# SingleBoardCircuitRev2.net
KiCad netlist of a schematic drawn in Altium Designer
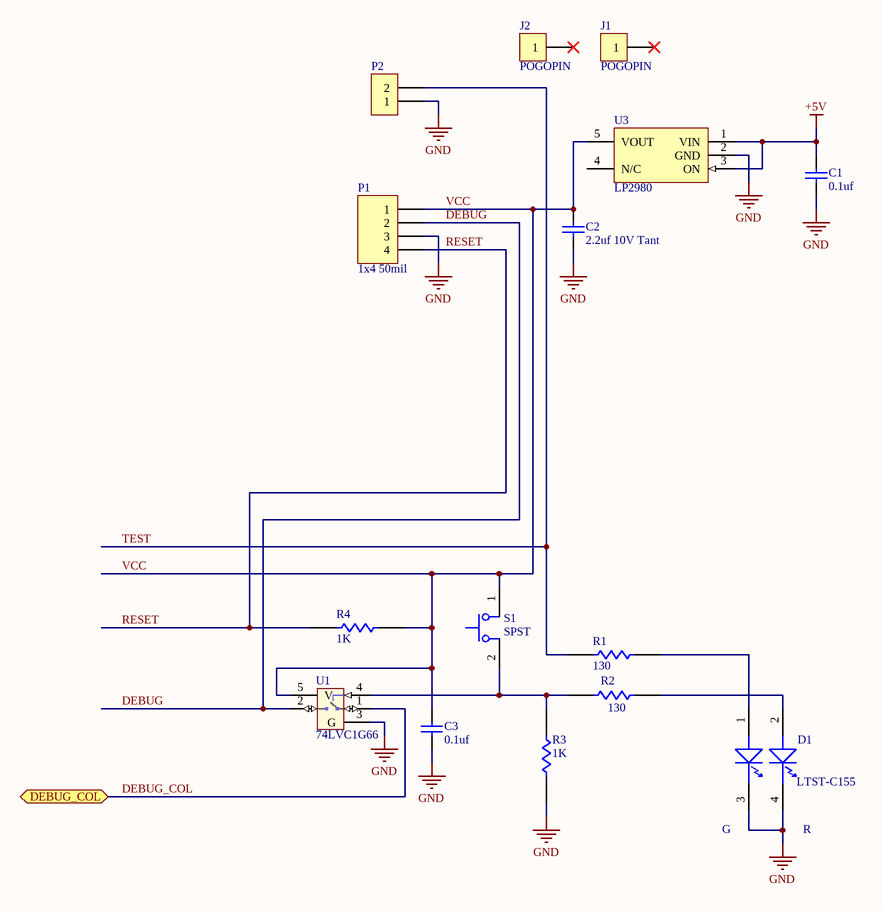
[diagram p0: SingleBoardCircuitRev2.SchDoc]

(export (version "E")
  (design (tool "Eeschema 10.0.6"))
  (components
    (comp (ref "C1")
      (value "0.1uf")
      (footprint "0603_072205")
      (description "Capacitor")
      (fields (field (name "PARTNO") "C0603C104Z3VACTU"))
      (libsource (lib "Miscellaneous Devices") (part "Cap"))
    )
    (comp (ref "C2")
      (value "2.2uf 10V Tant")
      (footprint "CAP A CASE_030205")
      (description "Capacitor")
      (fields (field (name "PARTNO") "F931A225MAA"))
      (libsource (lib "Miscellaneous Devices") (part "Cap"))
    )
    (comp (ref "C3")
      (value "0.1uf")
      (footprint "0603_072205")
      (description "Capacitor")
      (fields (field (name "PARTNO") "C0603C104Z3VACTU"))
      (libsource (lib "Miscellaneous Devices") (part "Cap"))
    )
    (comp (ref "D1")
      (value "LTST-C155")
      (footprint "LED 5mm x 2.5mm_061112")
      (fields (field (name "PARTNO") "LTST-C155GEKT"))
      (libsource (lib "Discrete") (part "LED_BI_2_1"))
    )
    (comp (ref "J1")
      (value "POGOPIN")
      (footprint "TestPoint52x32")
      (description "Connector")
      (libsource (lib "Common") (part "CON1"))
    )
    (comp (ref "J2")
      (value "POGOPIN")
      (footprint "TestPoint52x32")
      (description "Connector")
      (libsource (lib "Common") (part "CON1"))
    )
    (comp (ref "P1")
      (value "1x4 50mil")
      (footprint "1X4 HEADER_50mil_071411")
      (description "Header, 4-Pin")
      (libsource (lib "Miscellaneous Connectors") (part "Header 4"))
    )
    (comp (ref "P2")
      (value "1x2 50mil")
      (footprint "1X2 HEADER_50MIL_081611")
      (libsource (lib "Common") (part "CON2"))
    )
    (comp (ref "R1")
      (value "130")
      (footprint "0603_072205")
      (fields (field (name "PARTNO") "MCR03EZPFX1300"))
      (libsource (lib "Discrete") (part "RESISTOR"))
    )
    (comp (ref "R2")
      (value "130")
      (footprint "0603_072205")
      (fields (field (name "PARTNO") "MCR03EZPFX1300"))
      (libsource (lib "Discrete") (part "RESISTOR"))
    )
    (comp (ref "R3")
      (value "1K")
      (footprint "0603_072205")
      (fields (field (name "PARTNO") "MCR03EZPFX1001"))
      (libsource (lib "Discrete") (part "RESISTOR"))
    )
    (comp (ref "R4")
      (value "1K")
      (footprint "0603_072205")
      (fields (field (name "PARTNO") "MCR03EZPFX1001"))
      (libsource (lib "Discrete") (part "RESISTOR"))
    )
    (comp (ref "S1")
      (value "SPST")
      (footprint "SwitchDPDT_6_061412")
      (fields (field (name "PARTNO") "PVA2 EE H1"))
      (libsource (lib "Common") (part "SWITCH PB"))
    )
    (comp (ref "U1")
      (value "74LVC1G66")
      (footprint "SOT25_030205")
      (description "Single Solid State Switch")
      (fields (field (name "PARTNO") "SN74LVC1G66DBVR"))
      (libsource (lib "Common") (part "7466_SINGLE"))
    )
    (comp (ref "U3")
      (value "LP2980")
      (footprint "SOT25_030205")
      (fields (field (name "PARTNO") "LP2980AIM5-3.3/NOPB"))
      (libsource (lib "Common") (part "LP2985"))
    )
  )
  (nets
    (net (code "1") (name "+5V") (class "Default")
      (node (ref "C1") (pin "1") (pinfunction "1_1") (pintype "passive"))
      (node (ref "U3") (pin "1") (pinfunction "VIN_1") (pintype "power_in"))
      (node (ref "U3") (pin "3") (pinfunction "ON_3") (pintype "input"))
    )
    (net (code "2") (name "/DEBUG") (class "Default")
      (node (ref "P1") (pin "2") (pinfunction "2_2") (pintype "passive"))
      (node (ref "U1") (pin "2") (pinfunction "OUTY_2") (pintype "bidirectional"))
    )
    (net (code "3") (name "/DEBUG_COL") (class "Default")
      (node (ref "U1") (pin "1") (pinfunction "INA_1") (pintype "bidirectional"))
    )
    (net (code "4") (name "/RESET") (class "Default")
      (node (ref "P1") (pin "4") (pinfunction "4_4") (pintype "passive"))
      (node (ref "R4") (pin "1") (pinfunction "1_1") (pintype "passive"))
    )
    (net (code "5") (name "/TEST") (class "Default")
      (node (ref "P2") (pin "2") (pinfunction "2_2") (pintype "passive"))
      (node (ref "R1") (pin "2") (pinfunction "2_2") (pintype "passive"))
    )
    (net (code "6") (name "/VCC") (class "Default")
      (node (ref "C2") (pin "1") (pinfunction "1_1") (pintype "passive"))
      (node (ref "C3") (pin "1") (pinfunction "1_1") (pintype "passive"))
      (node (ref "P1") (pin "1") (pinfunction "1_1") (pintype "passive"))
      (node (ref "R4") (pin "2") (pinfunction "2_2") (pintype "passive"))
      (node (ref "S1") (pin "1") (pinfunction "1_1") (pintype "passive"))
      (node (ref "U1") (pin "5") (pinfunction "V_5") (pintype "power_in"))
      (node (ref "U3") (pin "5") (pinfunction "VOUT_5") (pintype "power_in"))
    )
    (net (code "7") (name "GND") (class "Default")
      (node (ref "C1") (pin "2") (pinfunction "2_2") (pintype "passive"))
      (node (ref "C2") (pin "2") (pinfunction "2_2") (pintype "passive"))
      (node (ref "C3") (pin "2") (pinfunction "2_2") (pintype "passive"))
      (node (ref "D1") (pin "3") (pinfunction "K_3") (pintype "passive"))
      (node (ref "D1") (pin "4") (pinfunction "K_4") (pintype "passive"))
      (node (ref "P1") (pin "3") (pinfunction "3_3") (pintype "passive"))
      (node (ref "P2") (pin "1") (pinfunction "1_1") (pintype "passive"))
      (node (ref "R3") (pin "1") (pinfunction "1_1") (pintype "passive"))
      (node (ref "U1") (pin "3") (pinfunction "G_3") (pintype "power_in"))
      (node (ref "U3") (pin "2") (pinfunction "GND_2") (pintype "power_in"))
    )
    (net (code "8") (name "Net-(D1-G)") (class "Default")
      (node (ref "D1") (pin "1") (pinfunction "G_1") (pintype "passive"))
      (node (ref "R1") (pin "1") (pinfunction "1_1") (pintype "passive"))
    )
    (net (code "9") (name "Net-(D1-R)") (class "Default")
      (node (ref "D1") (pin "2") (pinfunction "R_2") (pintype "passive"))
      (node (ref "R2") (pin "1") (pinfunction "1_1") (pintype "passive"))
    )
    (net (code "10") (name "Net-(U1-EN)") (class "Default")
      (node (ref "R2") (pin "2") (pinfunction "2_2") (pintype "passive"))
      (node (ref "R3") (pin "2") (pinfunction "2_2") (pintype "passive"))
      (node (ref "S1") (pin "2") (pinfunction "2_2") (pintype "passive"))
      (node (ref "U1") (pin "4") (pinfunction "EN_4") (pintype "input"))
    )
    (net (code "11") (name "unconnected-(J1-Pad1)") (class "Default")
      (node (ref "J1") (pin "1") (pinfunction "1_1") (pintype "passive+no_connect"))
    )
    (net (code "12") (name "unconnected-(J2-Pad1)") (class "Default")
      (node (ref "J2") (pin "1") (pinfunction "1_1") (pintype "passive+no_connect"))
    )
    (net (code "13") (name "unconnected-(U3-N{slash}C-Pad4)") (class "Default")
      (node (ref "U3") (pin "4") (pinfunction "N/C_4") (pintype "passive"))
    )
  )
)
